# Air_sensor_SD_card.net
KiCad netlist of a schematic drawn in Altium Designer
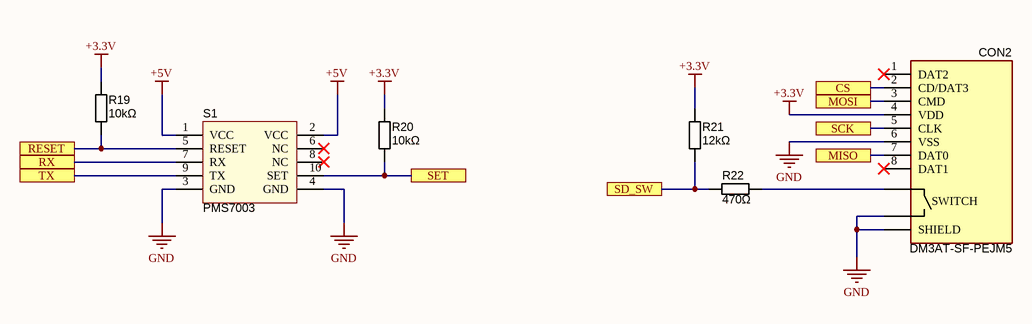
[diagram p0: Air sensor, SD card.SchDoc]

(export (version "E")
  (design (tool "Eeschema 10.0.6"))
  (components
    (comp (ref "CON2")
      (value "DM3AT-SF-PEJM5")
      (footprint "DM3ATSFPEJM5")
      (description "Connector")
      (libsource (lib "Nejc Klanjšček") (part "DM3AT-SF-PEJM5"))
    )
    (comp (ref "R19")
      (value "10kΩ")
      (footprint "RESC1608N")
      (description "Resistor SMD chip 1.5k Ohm 0.1W 5% 0603")
      (fields (field (name "TOLERANCE") "±5%") (field (name "Comment") "Thick Film"))
      (libsource (lib "") (part "RES_1K5_0603_5%_1"))
    )
    (comp (ref "R20")
      (value "10kΩ")
      (footprint "RESC1608N")
      (description "Resistor SMD chip 1.5k Ohm 0.1W 5% 0603")
      (fields (field (name "TOLERANCE") "±5%") (field (name "Comment") "Thick Film"))
      (libsource (lib "") (part "RES_1K5_0603_5%_1"))
    )
    (comp (ref "R21")
      (value "12kΩ")
      (footprint "RESC1608N")
      (description "Resistor SMD chip 1.5k Ohm 0.1W 5% 0603")
      (fields (field (name "TOLERANCE") "±5%") (field (name "Comment") "Thick Film"))
      (libsource (lib "") (part "RES_1K5_0603_5%_1"))
    )
    (comp (ref "R22")
      (value "470Ω")
      (footprint "RESC1608N")
      (description "Resistor SMD chip 1.5k Ohm 0.1W 5% 0603")
      (fields (field (name "TOLERANCE") "±5%") (field (name "Comment") "Thick Film"))
      (libsource (lib "Nejc Klanjšček") (part "RES_1K5_0603_5%"))
    )
    (comp (ref "S1")
      (value "PMS7003")
      (footprint "PMS7003")
      (libsource (lib "Nejc Klanjšček") (part "PMS7003"))
    )
  )
  (nets
    (net (code "1") (name "+3.3V") (class "Default")
      (node (ref "CON2") (pin "4") (pinfunction "VDD_4") (pintype "passive"))
      (node (ref "R19") (pin "2") (pinfunction "2_2") (pintype "passive"))
      (node (ref "R20") (pin "2") (pinfunction "2_2") (pintype "passive"))
      (node (ref "R21") (pin "2") (pinfunction "2_2") (pintype "passive"))
    )
    (net (code "2") (name "+5V") (class "Default")
      (node (ref "S1") (pin "1") (pinfunction "VCC_1") (pintype "passive"))
      (node (ref "S1") (pin "2") (pinfunction "VCC_2") (pintype "passive"))
    )
    (net (code "3") (name "/CS") (class "Default")
      (node (ref "CON2") (pin "2") (pinfunction "CD/DAT3_2") (pintype "passive"))
    )
    (net (code "4") (name "/MISO") (class "Default")
      (node (ref "CON2") (pin "7") (pinfunction "DAT0_7") (pintype "passive"))
    )
    (net (code "5") (name "/MOSI") (class "Default")
      (node (ref "CON2") (pin "3") (pinfunction "CMD_3") (pintype "passive"))
    )
    (net (code "6") (name "/RESET") (class "Default")
      (node (ref "R19") (pin "1") (pinfunction "1_1") (pintype "passive"))
      (node (ref "S1") (pin "5") (pinfunction "RESET_5") (pintype "passive"))
    )
    (net (code "7") (name "/RX") (class "Default")
      (node (ref "S1") (pin "7") (pinfunction "RX_7") (pintype "passive"))
    )
    (net (code "8") (name "/SCK") (class "Default")
      (node (ref "CON2") (pin "5") (pinfunction "CLK_5") (pintype "passive"))
    )
    (net (code "9") (name "/SD_SW") (class "Default")
      (node (ref "R21") (pin "1") (pinfunction "1_1") (pintype "passive"))
      (node (ref "R22") (pin "2") (pinfunction "2_2") (pintype "passive"))
    )
    (net (code "10") (name "/SET") (class "Default")
      (node (ref "R20") (pin "1") (pinfunction "1_1") (pintype "passive"))
      (node (ref "S1") (pin "10") (pinfunction "SET_10") (pintype "passive"))
    )
    (net (code "11") (name "/TX") (class "Default")
      (node (ref "S1") (pin "9") (pinfunction "TX_9") (pintype "passive"))
    )
    (net (code "12") (name "GND") (class "Default")
      (node (ref "CON2") (pin "10") (pinfunction "SW_2_10") (pintype "passive"))
      (node (ref "CON2") (pin "6") (pinfunction "VSS_6") (pintype "passive"))
      (node (ref "CON2") (pin "GND") (pinfunction "SHIELD_GND") (pintype "passive"))
      (node (ref "S1") (pin "3") (pinfunction "GND_3") (pintype "passive"))
      (node (ref "S1") (pin "4") (pinfunction "GND_4") (pintype "passive"))
    )
    (net (code "13") (name "Net-(CON2-SW_1)") (class "Default")
      (node (ref "CON2") (pin "9") (pinfunction "SW_1_9") (pintype "passive"))
      (node (ref "R22") (pin "1") (pinfunction "1_1") (pintype "passive"))
    )
    (net (code "14") (name "unconnected-(CON2-DAT1-Pad8)") (class "Default")
      (node (ref "CON2") (pin "8") (pinfunction "DAT1_8") (pintype "passive+no_connect"))
    )
    (net (code "15") (name "unconnected-(CON2-DAT2-Pad1)") (class "Default")
      (node (ref "CON2") (pin "1") (pinfunction "DAT2_1") (pintype "passive+no_connect"))
    )
    (net (code "16") (name "unconnected-(S1-NC-Pad6)") (class "Default")
      (node (ref "S1") (pin "6") (pinfunction "NC_6") (pintype "passive+no_connect"))
    )
    (net (code "17") (name "unconnected-(S1-NC-Pad8)") (class "Default")
      (node (ref "S1") (pin "8") (pinfunction "NC_8") (pintype "passive+no_connect"))
    )
  )
)
